# K-Diag_-_double.net
KiCad netlist of a schematic drawn in EAGLE
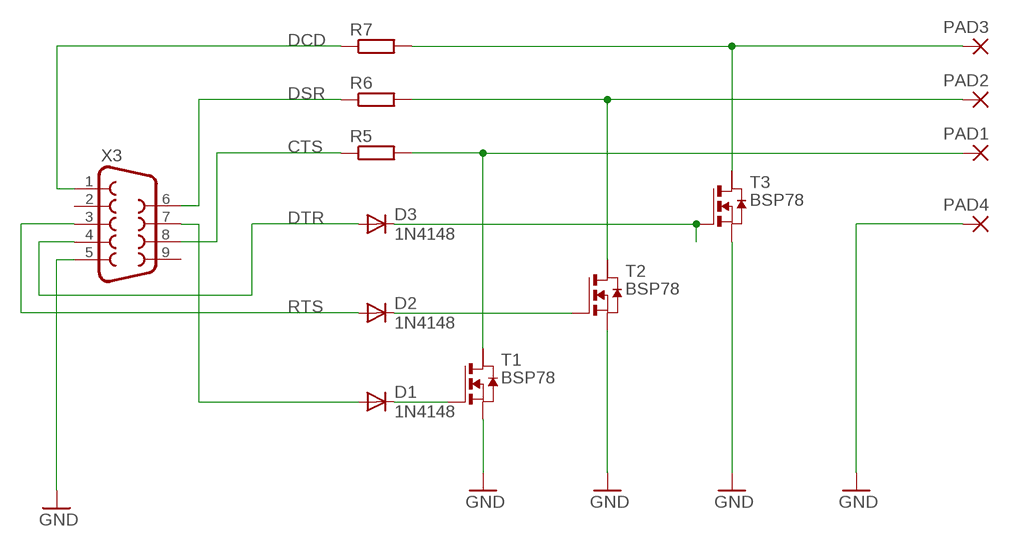
[diagram p0: schematic, sheet 1]

(export (version "E")
  (design (tool "Eeschema 10.0.6"))
  (components
    (comp (ref "D1")
      (value "1N4148")
      (footprint "eagle-import:DO214AC")
      (libsource (lib "eagle-import") (part "DIODE-DO214AC"))
    )
    (comp (ref "D2")
      (value "1N4148")
      (footprint "eagle-import:DO214AC")
      (libsource (lib "eagle-import") (part "DIODE-DO214AC"))
    )
    (comp (ref "D3")
      (value "1N4148")
      (footprint "eagle-import:DO214AC")
      (libsource (lib "eagle-import") (part "DIODE-DO214AC"))
    )
    (comp (ref "PAD1")
      (value "2,54/0,8")
      (footprint "eagle-import:2,54_0,8")
      (libsource (lib "eagle-import") (part "2,54/0,8"))
    )
    (comp (ref "PAD2")
      (value "2,54/0,8")
      (footprint "eagle-import:2,54_0,8")
      (libsource (lib "eagle-import") (part "2,54/0,8"))
    )
    (comp (ref "PAD3")
      (value "2,54/0,8")
      (footprint "eagle-import:2,54_0,8")
      (libsource (lib "eagle-import") (part "2,54/0,8"))
    )
    (comp (ref "PAD4")
      (value "2,54/0,8")
      (footprint "eagle-import:2,54_0,8")
      (libsource (lib "eagle-import") (part "2,54/0,8"))
    )
    (comp (ref "R5")
      (value "R-EU_R0805")
      (footprint "eagle-import:R0805")
      (libsource (lib "eagle-import") (part "R-EU_R0805"))
    )
    (comp (ref "R6")
      (value "R-EU_R0805")
      (footprint "eagle-import:R0805")
      (libsource (lib "eagle-import") (part "R-EU_R0805"))
    )
    (comp (ref "R7")
      (value "R-EU_R0805")
      (footprint "eagle-import:R0805")
      (libsource (lib "eagle-import") (part "R-EU_R0805"))
    )
    (comp (ref "T1")
      (value "BSP78")
      (footprint "eagle-import:SOT223")
      (libsource (lib "eagle-import") (part "NMOSSOT223"))
    )
    (comp (ref "T2")
      (value "BSP78")
      (footprint "eagle-import:SOT223")
      (libsource (lib "eagle-import") (part "NMOSSOT223"))
    )
    (comp (ref "T3")
      (value "BSP78")
      (footprint "eagle-import:SOT223")
      (libsource (lib "eagle-import") (part "NMOSSOT223"))
    )
    (comp (ref "X3")
      (value "F09D")
      (footprint "eagle-import:F09D")
      (libsource (lib "eagle-import") (part "F09D"))
    )
  )
  (nets
    (net (code "1") (name "/CTS") (class "Default")
      (node (ref "R5") (pin "1") (pinfunction "1_1") (pintype "passive"))
      (node (ref "X3") (pin "8") (pinfunction "8_8") (pintype "passive"))
    )
    (net (code "2") (name "/DCD") (class "Default")
      (node (ref "R7") (pin "1") (pinfunction "1_1") (pintype "passive"))
      (node (ref "X3") (pin "1") (pinfunction "1_1") (pintype "passive"))
    )
    (net (code "3") (name "/DSR") (class "Default")
      (node (ref "R6") (pin "1") (pinfunction "1_1") (pintype "passive"))
      (node (ref "X3") (pin "6") (pinfunction "6_6") (pintype "passive"))
    )
    (net (code "4") (name "/DTR") (class "Default")
      (node (ref "D3") (pin "A") (pinfunction "A_A") (pintype "passive"))
      (node (ref "X3") (pin "4") (pinfunction "4_4") (pintype "passive"))
    )
    (net (code "5") (name "/RTS") (class "Default")
      (node (ref "D2") (pin "A") (pinfunction "A_A") (pintype "passive"))
      (node (ref "X3") (pin "3") (pinfunction "3_3") (pintype "passive"))
    )
    (net (code "6") (name "GND") (class "Default")
      (node (ref "PAD4") (pin "1") (pinfunction "P_1") (pintype "passive"))
      (node (ref "T1") (pin "3") (pinfunction "S_3") (pintype "passive"))
      (node (ref "T2") (pin "3") (pinfunction "S_3") (pintype "passive"))
      (node (ref "T3") (pin "3") (pinfunction "S_3") (pintype "passive"))
      (node (ref "X3") (pin "5") (pinfunction "5_5") (pintype "passive"))
    )
    (net (code "7") (name "Net-(D1-PadA)") (class "Default")
      (node (ref "D1") (pin "A") (pinfunction "A_A") (pintype "passive"))
      (node (ref "X3") (pin "7") (pinfunction "7_7") (pintype "passive"))
    )
    (net (code "8") (name "Net-(PAD1-P)") (class "Default")
      (node (ref "PAD1") (pin "1") (pinfunction "P_1") (pintype "passive"))
      (node (ref "R5") (pin "2") (pinfunction "2_2") (pintype "passive"))
      (node (ref "T1") (pin "2") (pinfunction "D_2") (pintype "passive"))
    )
    (net (code "9") (name "Net-(PAD2-P)") (class "Default")
      (node (ref "PAD2") (pin "1") (pinfunction "P_1") (pintype "passive"))
      (node (ref "R6") (pin "2") (pinfunction "2_2") (pintype "passive"))
      (node (ref "T2") (pin "2") (pinfunction "D_2") (pintype "passive"))
    )
    (net (code "10") (name "Net-(PAD3-P)") (class "Default")
      (node (ref "PAD3") (pin "1") (pinfunction "P_1") (pintype "passive"))
      (node (ref "R7") (pin "2") (pinfunction "2_2") (pintype "passive"))
      (node (ref "T3") (pin "2") (pinfunction "D_2") (pintype "passive"))
    )
    (net (code "11") (name "Net-(T1-G)") (class "Default")
      (node (ref "D1") (pin "C") (pinfunction "C_C") (pintype "passive"))
      (node (ref "T1") (pin "1") (pinfunction "G_1") (pintype "passive"))
    )
    (net (code "12") (name "Net-(T2-G)") (class "Default")
      (node (ref "D2") (pin "C") (pinfunction "C_C") (pintype "passive"))
      (node (ref "T2") (pin "1") (pinfunction "G_1") (pintype "passive"))
    )
    (net (code "13") (name "Net-(T3-G)") (class "Default")
      (node (ref "D3") (pin "C") (pinfunction "C_C") (pintype "passive"))
      (node (ref "T3") (pin "1") (pinfunction "G_1") (pintype "passive"))
    )
    (net (code "14") (name "unconnected-(T1-D2-Pad4)") (class "Default")
      (node (ref "T1") (pin "4") (pinfunction "D2_4") (pintype "passive"))
    )
    (net (code "15") (name "unconnected-(T2-D2-Pad4)") (class "Default")
      (node (ref "T2") (pin "4") (pinfunction "D2_4") (pintype "passive"))
    )
    (net (code "16") (name "unconnected-(T3-D2-Pad4)") (class "Default")
      (node (ref "T3") (pin "4") (pinfunction "D2_4") (pintype "passive"))
    )
    (net (code "17") (name "unconnected-(X3-Pad2)") (class "Default")
      (node (ref "X3") (pin "2") (pinfunction "2_2") (pintype "passive"))
    )
    (net (code "18") (name "unconnected-(X3-Pad9)") (class "Default")
      (node (ref "X3") (pin "9") (pinfunction "9_9") (pintype "passive"))
    )
  )
)
